# connerctor_3-5v.net
KiCad netlist of a schematic drawn in Altium Designer
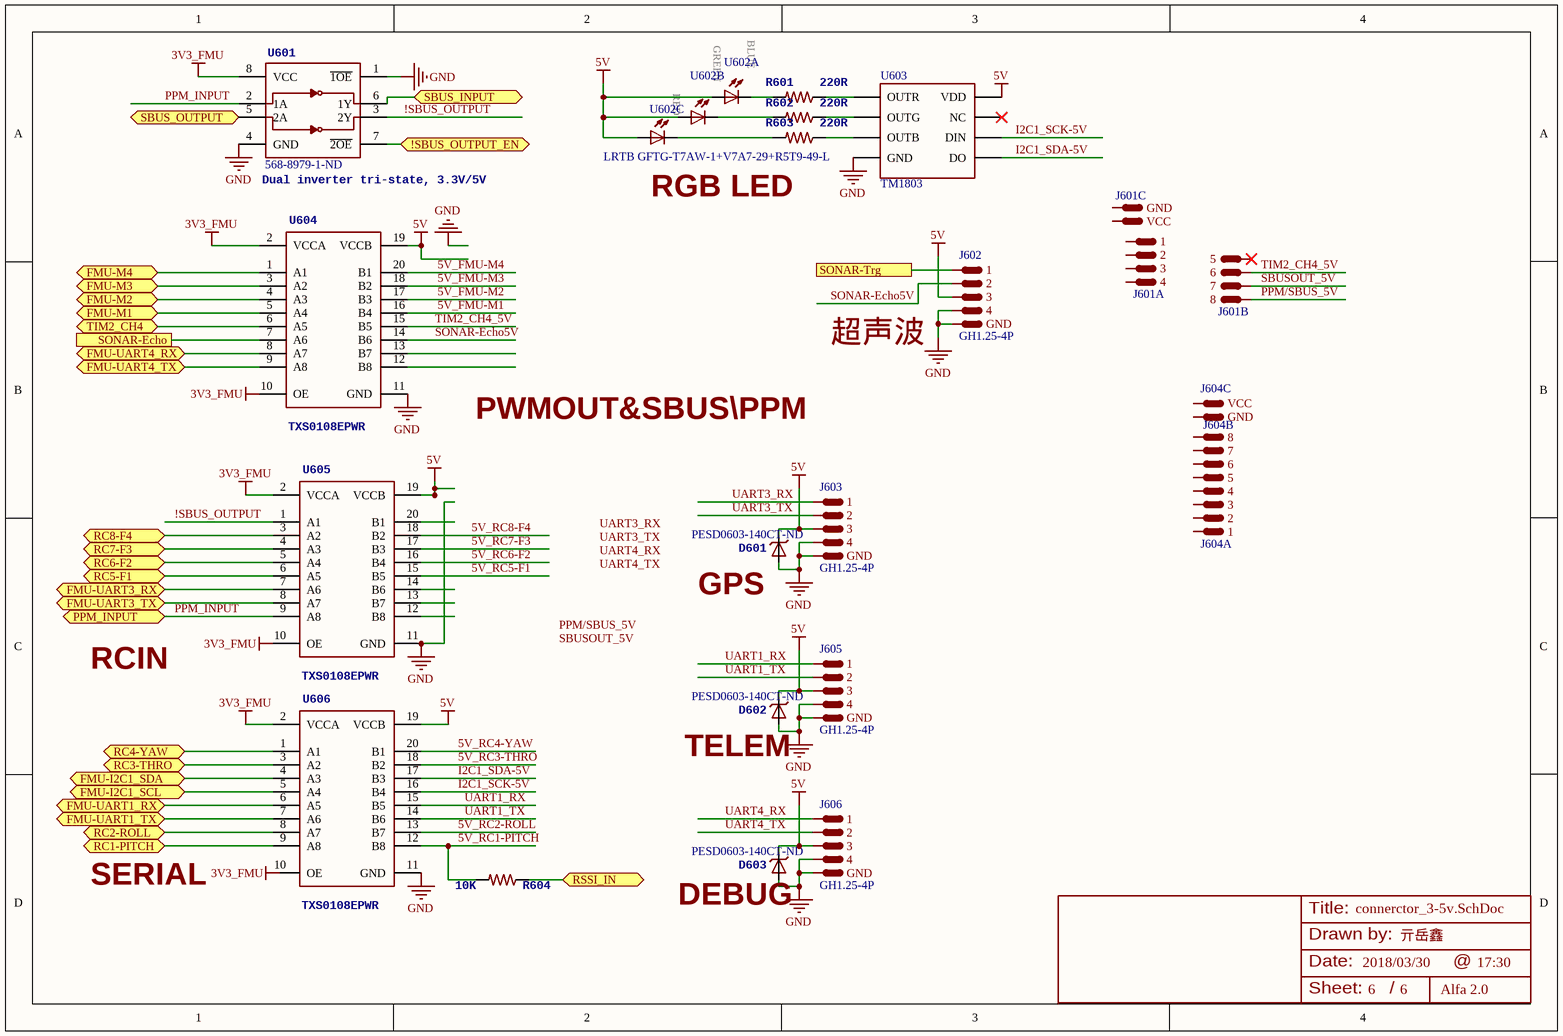
[diagram p0: connerctor_3-5v.SchDoc]

(export (version "E")
  (design (tool "Eeschema 10.0.6"))
  (components
    (comp (ref "D601")
      (value "PESD0603-140")
      (footprint "0603-ESD")
      (description "TVS DIODE 14V 0603")
      (fields (field (name "SUPPLIER PART NUMBER 1") "PESD0603-140CT-ND"))
      (libsource (lib "Q's无源元件类") (part "DIODE-ESD"))
    )
    (comp (ref "D602")
      (value "PESD0603-140")
      (footprint "0603-ESD")
      (description "TVS DIODE 14V 0603")
      (fields (field (name "SUPPLIER PART NUMBER 1") "PESD0603-140CT-ND"))
      (libsource (lib "Q's无源元件类") (part "DIODE-ESD"))
    )
    (comp (ref "D603")
      (value "PESD0603-140")
      (footprint "0603-ESD")
      (description "TVS DIODE 14V 0603")
      (fields (field (name "SUPPLIER PART NUMBER 1") "PESD0603-140CT-ND"))
      (libsource (lib "Q's无源元件类") (part "DIODE-ESD"))
    )
    (comp (ref "J601")
      (value "JR 3X8")
      (footprint "JR3X8")
      (description "Header 3X8 pins")
      (libsource (lib "Q's端子及图标") (part "JR 3X8"))
    )
    (comp (ref "J602")
      (value "GH1.25-4P")
      (footprint "1.25-4P")
      (description "GH1.25mm 立贴 间距1.25mm 连接器贴片")
      (libsource (lib "Q's端子及图标") (part "GH1.25-4P"))
    )
    (comp (ref "J603")
      (value "GH1.25-4P")
      (footprint "1.25-4P")
      (description "GH1.25mm 立贴 间距1.25mm 连接器贴片")
      (libsource (lib "Q's端子及图标") (part "GH1.25-4P"))
    )
    (comp (ref "J604")
      (value "JR 3X8")
      (footprint "JR3X8")
      (description "Header 3X8 pins")
      (libsource (lib "Q's端子及图标") (part "JR 3X8"))
    )
    (comp (ref "J605")
      (value "GH1.25-4P")
      (footprint "1.25-4P")
      (description "GH1.25mm 立贴 间距1.25mm 连接器贴片")
      (libsource (lib "Q's端子及图标") (part "GH1.25-4P"))
    )
    (comp (ref "J606")
      (value "GH1.25-4P")
      (footprint "1.25-4P")
      (description "GH1.25mm 立贴 间距1.25mm 连接器贴片")
      (libsource (lib "Q's端子及图标") (part "GH1.25-4P"))
    )
    (comp (ref "R601")
      (value "220R")
      (footprint "0603-RES")
      (description "RES 220R OHM 1/10W 5% 0603")
      (libsource (lib "Q's无源元件类") (part "RES0603-220R"))
    )
    (comp (ref "R602")
      (value "220R")
      (footprint "0603-RES")
      (description "RES 220R OHM 1/10W 5% 0603")
      (libsource (lib "Q's无源元件类") (part "RES0603-220R"))
    )
    (comp (ref "R603")
      (value "220R")
      (footprint "0603-RES")
      (description "RES 220R OHM 1/10W 5% 0603")
      (libsource (lib "Q's无源元件类") (part "RES0603-220R"))
    )
    (comp (ref "R604")
      (value "10K")
      (footprint "0603-RES")
      (description "RES 10K OHM 1/10W 5% 0603")
      (libsource (lib "Q's无源元件类") (part "RES0603-10K"))
    )
    (comp (ref "U601")
      (value "Dual inverter tri-state, 3.3V/5V")
      (footprint "TSSOP8_SOT505-2")
      (description "IC INVERTER DUAL 4-INPUT 8TSSOP")
      (fields
        (field (name "3DR_PARTNO") "ECM0817")
        (field (name "PARTNO") "74LVC2G240DP,125")
        (field (name "SUPPLIER PART NUMBER 1") "568-8979-1-ND")
      )
      (libsource (lib "Q's有源芯片类") (part "74LVC2G240-TSSOP-8"))
    )
    (comp (ref "U602")
      (value "LRTB GFTG-T7AW-1+V7A7-29+R5T9-49-L")
      (footprint "P-LCC-6")
      (description "Muti LEDs")
      (libsource (lib "Q's无源元件类") (part "LED-RGB"))
    )
    (comp (ref "U603")
      (value "TM1803")
      (footprint "SO08")
      (description "3-Channel Constant-Current LED Driver")
      (libsource (lib "Q's有源芯片类") (part "LED_DRV-TM1803"))
    )
    (comp (ref "U604")
      (value "TXS0108EPWR")
      (footprint "SOP65P640-20N")
      (description "IC XLATR VOLT-LVL 8B BDIR 20SOP")
      (libsource (lib "Q's有源芯片类") (part "TXS0108EPWR"))
    )
    (comp (ref "U605")
      (value "TXS0108EPWR")
      (footprint "SOP65P640-20N")
      (description "IC XLATR VOLT-LVL 8B BDIR 20SOP")
      (libsource (lib "Q's有源芯片类") (part "TXS0108EPWR"))
    )
    (comp (ref "U606")
      (value "TXS0108EPWR")
      (footprint "SOP65P640-20N")
      (description "IC XLATR VOLT-LVL 8B BDIR 20SOP")
      (libsource (lib "Q's有源芯片类") (part "TXS0108EPWR"))
    )
  )
  (nets
    (net (code "1") (name "/!SBUS_OUTPUT") (class "Default")
      (node (ref "U601") (pin "3") (pinfunction "2Y_3") (pintype "passive"))
      (node (ref "U605") (pin "1") (pinfunction "A1_1") (pintype "passive"))
    )
    (net (code "2") (name "/!SBUS_OUTPUT_EN") (class "Default")
      (node (ref "U601") (pin "7") (pinfunction "~{2OE}_7") (pintype "passive"))
    )
    (net (code "3") (name "/5V_FMU-M1") (class "Default")
      (node (ref "U604") (pin "16") (pinfunction "B4_16") (pintype "passive"))
    )
    (net (code "4") (name "/5V_FMU-M2") (class "Default")
      (node (ref "U604") (pin "17") (pinfunction "B3_17") (pintype "passive"))
    )
    (net (code "5") (name "/5V_FMU-M3") (class "Default")
      (node (ref "U604") (pin "18") (pinfunction "B2_18") (pintype "passive"))
    )
    (net (code "6") (name "/5V_FMU-M4") (class "Default")
      (node (ref "U604") (pin "20") (pinfunction "B1_20") (pintype "passive"))
    )
    (net (code "7") (name "/5V_RC1-PITCH") (class "Default")
      (node (ref "R604") (pin "2") (pinfunction "2_2") (pintype "passive"))
      (node (ref "U606") (pin "12") (pinfunction "B8_12") (pintype "passive"))
    )
    (net (code "8") (name "/5V_RC2-ROLL") (class "Default")
      (node (ref "U606") (pin "13") (pinfunction "B7_13") (pintype "passive"))
    )
    (net (code "9") (name "/5V_RC3-THRO") (class "Default")
      (node (ref "U606") (pin "18") (pinfunction "B2_18") (pintype "passive"))
    )
    (net (code "10") (name "/5V_RC4-YAW") (class "Default")
      (node (ref "U606") (pin "20") (pinfunction "B1_20") (pintype "passive"))
    )
    (net (code "11") (name "/5V_RC5-F1") (class "Default")
      (node (ref "U605") (pin "15") (pinfunction "B5_15") (pintype "passive"))
    )
    (net (code "12") (name "/5V_RC6-F2") (class "Default")
      (node (ref "U605") (pin "16") (pinfunction "B4_16") (pintype "passive"))
    )
    (net (code "13") (name "/5V_RC7-F3") (class "Default")
      (node (ref "U605") (pin "17") (pinfunction "B3_17") (pintype "passive"))
    )
    (net (code "14") (name "/5V_RC8-F4") (class "Default")
      (node (ref "U605") (pin "18") (pinfunction "B2_18") (pintype "passive"))
    )
    (net (code "15") (name "/FMU-I2C1_SCL") (class "Default")
      (node (ref "U606") (pin "5") (pinfunction "A4_5") (pintype "passive"))
    )
    (net (code "16") (name "/FMU-I2C1_SDA") (class "Default")
      (node (ref "U606") (pin "4") (pinfunction "A3_4") (pintype "passive"))
    )
    (net (code "17") (name "/FMU-M1") (class "Default")
      (node (ref "U604") (pin "5") (pinfunction "A4_5") (pintype "passive"))
    )
    (net (code "18") (name "/FMU-M2") (class "Default")
      (node (ref "U604") (pin "4") (pinfunction "A3_4") (pintype "passive"))
    )
    (net (code "19") (name "/FMU-M3") (class "Default")
      (node (ref "U604") (pin "3") (pinfunction "A2_3") (pintype "passive"))
    )
    (net (code "20") (name "/FMU-M4") (class "Default")
      (node (ref "U604") (pin "1") (pinfunction "A1_1") (pintype "passive"))
    )
    (net (code "21") (name "/FMU-UART1_RX") (class "Default")
      (node (ref "U606") (pin "6") (pinfunction "A5_6") (pintype "passive"))
    )
    (net (code "22") (name "/FMU-UART1_TX") (class "Default")
      (node (ref "U606") (pin "7") (pinfunction "A6_7") (pintype "passive"))
    )
    (net (code "23") (name "/FMU-UART3_RX") (class "Default")
      (node (ref "U605") (pin "7") (pinfunction "A6_7") (pintype "passive"))
    )
    (net (code "24") (name "/FMU-UART3_TX") (class "Default")
      (node (ref "U605") (pin "8") (pinfunction "A7_8") (pintype "passive"))
    )
    (net (code "25") (name "/FMU-UART4_RX") (class "Default")
      (node (ref "U604") (pin "8") (pinfunction "A7_8") (pintype "passive"))
    )
    (net (code "26") (name "/FMU-UART4_TX") (class "Default")
      (node (ref "U604") (pin "9") (pinfunction "A8_9") (pintype "passive"))
    )
    (net (code "27") (name "/I2C1_SCK-5V") (class "Default")
      (node (ref "U603") (pin "6") (pinfunction "DIN_6") (pintype "passive"))
      (node (ref "U606") (pin "16") (pinfunction "B4_16") (pintype "passive"))
    )
    (net (code "28") (name "/I2C1_SDA-5V") (class "Default")
      (node (ref "U603") (pin "5") (pinfunction "DO_5") (pintype "passive"))
      (node (ref "U606") (pin "17") (pinfunction "B3_17") (pintype "passive"))
    )
    (net (code "29") (name "/PPM_INPUT") (class "Default")
      (node (ref "U601") (pin "2") (pinfunction "1A_2") (pintype "passive"))
      (node (ref "U605") (pin "9") (pinfunction "A8_9") (pintype "passive"))
    )
    (net (code "30") (name "/PPM{slash}SBUS_5V") (class "Default")
      (node (ref "J601") (pin "8") (pinfunction "8_8") (pintype "passive"))
    )
    (net (code "31") (name "/RC1-PITCH") (class "Default")
      (node (ref "U606") (pin "9") (pinfunction "A8_9") (pintype "passive"))
    )
    (net (code "32") (name "/RC2-ROLL") (class "Default")
      (node (ref "U606") (pin "8") (pinfunction "A7_8") (pintype "passive"))
    )
    (net (code "33") (name "/RC3-THRO") (class "Default")
      (node (ref "U606") (pin "3") (pinfunction "A2_3") (pintype "passive"))
    )
    (net (code "34") (name "/RC4-YAW") (class "Default")
      (node (ref "U606") (pin "1") (pinfunction "A1_1") (pintype "passive"))
    )
    (net (code "35") (name "/RC5-F1") (class "Default")
      (node (ref "U605") (pin "6") (pinfunction "A5_6") (pintype "passive"))
    )
    (net (code "36") (name "/RC6-F2") (class "Default")
      (node (ref "U605") (pin "5") (pinfunction "A4_5") (pintype "passive"))
    )
    (net (code "37") (name "/RC7-F3") (class "Default")
      (node (ref "U605") (pin "4") (pinfunction "A3_4") (pintype "passive"))
    )
    (net (code "38") (name "/RC8-F4") (class "Default")
      (node (ref "U605") (pin "3") (pinfunction "A2_3") (pintype "passive"))
    )
    (net (code "39") (name "/RSSI_IN") (class "Default")
      (node (ref "R604") (pin "1") (pinfunction "1_1") (pintype "passive"))
    )
    (net (code "40") (name "/SBUSOUT_5V") (class "Default")
      (node (ref "J601") (pin "7") (pinfunction "7_7") (pintype "passive"))
    )
    (net (code "41") (name "/SBUS_INPUT") (class "Default")
      (node (ref "U601") (pin "6") (pinfunction "1Y_6") (pintype "passive"))
    )
    (net (code "42") (name "/SBUS_OUTPUT") (class "Default")
      (node (ref "U601") (pin "5") (pinfunction "2A_5") (pintype "passive"))
    )
    (net (code "43") (name "/SONAR-Echo") (class "Default")
      (node (ref "U604") (pin "7") (pinfunction "A6_7") (pintype "passive"))
    )
    (net (code "44") (name "/SONAR-Echo5V") (class "Default")
      (node (ref "J602") (pin "2") (pinfunction "2_2") (pintype "passive"))
      (node (ref "U604") (pin "14") (pinfunction "B6_14") (pintype "passive"))
    )
    (net (code "45") (name "/SONAR-Trg") (class "Default")
      (node (ref "J602") (pin "1") (pinfunction "1_1") (pintype "passive"))
    )
    (net (code "46") (name "/TIM2_CH4") (class "Default")
      (node (ref "U604") (pin "6") (pinfunction "A5_6") (pintype "passive"))
    )
    (net (code "47") (name "/TIM2_CH4_5V") (class "Default")
      (node (ref "J601") (pin "6") (pinfunction "6_6") (pintype "passive"))
      (node (ref "U604") (pin "15") (pinfunction "B5_15") (pintype "passive"))
    )
    (net (code "48") (name "/UART1_RX") (class "Default")
      (node (ref "J605") (pin "1") (pinfunction "1_1") (pintype "passive"))
      (node (ref "U606") (pin "15") (pinfunction "B5_15") (pintype "passive"))
    )
    (net (code "49") (name "/UART1_TX") (class "Default")
      (node (ref "J605") (pin "2") (pinfunction "2_2") (pintype "passive"))
      (node (ref "U606") (pin "14") (pinfunction "B6_14") (pintype "passive"))
    )
    (net (code "50") (name "/UART3_RX") (class "Default")
      (node (ref "J603") (pin "1") (pinfunction "1_1") (pintype "passive"))
    )
    (net (code "51") (name "/UART3_TX") (class "Default")
      (node (ref "J603") (pin "2") (pinfunction "2_2") (pintype "passive"))
    )
    (net (code "52") (name "/UART4_RX") (class "Default")
      (node (ref "J606") (pin "1") (pinfunction "1_1") (pintype "passive"))
    )
    (net (code "53") (name "/UART4_TX") (class "Default")
      (node (ref "J606") (pin "2") (pinfunction "2_2") (pintype "passive"))
    )
    (net (code "54") (name "3V3_FMU") (class "Default")
      (node (ref "U601") (pin "8") (pinfunction "VCC_8") (pintype "power_in"))
      (node (ref "U604") (pin "10") (pinfunction "OE_10") (pintype "passive"))
      (node (ref "U604") (pin "2") (pinfunction "VCCA_2") (pintype "passive"))
      (node (ref "U605") (pin "10") (pinfunction "OE_10") (pintype "passive"))
      (node (ref "U605") (pin "2") (pinfunction "VCCA_2") (pintype "passive"))
      (node (ref "U606") (pin "2") (pinfunction "VCCA_2") (pintype "passive"))
    )
    (net (code "55") (name "5V") (class "Default")
      (node (ref "D601") (pin "C") (pinfunction "C_C") (pintype "passive"))
      (node (ref "D602") (pin "C") (pinfunction "C_C") (pintype "passive"))
      (node (ref "D603") (pin "C") (pinfunction "C_C") (pintype "passive"))
      (node (ref "J602") (pin "3") (pinfunction "3_3") (pintype "passive"))
      (node (ref "J603") (pin "3") (pinfunction "3_3") (pintype "passive"))
      (node (ref "J605") (pin "3") (pinfunction "3_3") (pintype "passive"))
      (node (ref "J606") (pin "3") (pinfunction "3_3") (pintype "passive"))
      (node (ref "U602") (pin "A1") (pinfunction "A_A1") (pintype "passive"))
      (node (ref "U602") (pin "A2") (pinfunction "A_A2") (pintype "passive"))
      (node (ref "U602") (pin "A3") (pinfunction "A_A3") (pintype "passive"))
      (node (ref "U603") (pin "8") (pinfunction "VDD_8") (pintype "passive"))
      (node (ref "U604") (pin "19") (pinfunction "VCCB_19") (pintype "passive"))
      (node (ref "U605") (pin "19") (pinfunction "VCCB_19") (pintype "passive"))
      (node (ref "U606") (pin "19") (pinfunction "VCCB_19") (pintype "passive"))
    )
    (net (code "56") (name "GND") (class "Default")
      (node (ref "D601") (pin "A") (pinfunction "A_A") (pintype "passive"))
      (node (ref "D602") (pin "A") (pinfunction "A_A") (pintype "passive"))
      (node (ref "D603") (pin "A") (pinfunction "A_A") (pintype "passive"))
      (node (ref "J602") (pin "4") (pinfunction "4_4") (pintype "passive"))
      (node (ref "J602") (pin "GND") (pinfunction "GND_GND") (pintype "passive"))
      (node (ref "J603") (pin "4") (pinfunction "4_4") (pintype "passive"))
      (node (ref "J603") (pin "GND") (pinfunction "GND_GND") (pintype "passive"))
      (node (ref "J605") (pin "4") (pinfunction "4_4") (pintype "passive"))
      (node (ref "J605") (pin "GND") (pinfunction "GND_GND") (pintype "passive"))
      (node (ref "J606") (pin "4") (pinfunction "4_4") (pintype "passive"))
      (node (ref "J606") (pin "GND") (pinfunction "GND_GND") (pintype "passive"))
      (node (ref "U601") (pin "1") (pinfunction "~{1OE}_1") (pintype "passive"))
      (node (ref "U601") (pin "4") (pinfunction "GND_4") (pintype "passive"))
      (node (ref "U603") (pin "4") (pinfunction "GND_4") (pintype "passive"))
      (node (ref "U604") (pin "11") (pinfunction "GND_11") (pintype "passive"))
      (node (ref "U605") (pin "11") (pinfunction "GND_11") (pintype "passive"))
      (node (ref "U606") (pin "11") (pinfunction "GND_11") (pintype "passive"))
    )
    (net (code "57") (name "Net-(U602A-C)") (class "Default")
      (node (ref "R601") (pin "2") (pinfunction "2_2") (pintype "passive"))
      (node (ref "U602") (pin "C1") (pinfunction "C_C1") (pintype "passive"))
    )
    (net (code "58") (name "Net-(U602B-C)") (class "Default")
      (node (ref "R602") (pin "2") (pinfunction "2_2") (pintype "passive"))
      (node (ref "U602") (pin "C2") (pinfunction "C_C2") (pintype "passive"))
    )
    (net (code "59") (name "Net-(U602C-C)") (class "Default")
      (node (ref "R603") (pin "2") (pinfunction "2_2") (pintype "passive"))
      (node (ref "U602") (pin "C3") (pinfunction "C_C3") (pintype "passive"))
    )
    (net (code "60") (name "Net-(U603-OUTB)") (class "Default")
      (node (ref "R603") (pin "1") (pinfunction "1_1") (pintype "passive"))
      (node (ref "U603") (pin "3") (pinfunction "OUTB_3") (pintype "passive"))
    )
    (net (code "61") (name "Net-(U603-OUTG)") (class "Default")
      (node (ref "R602") (pin "1") (pinfunction "1_1") (pintype "passive"))
      (node (ref "U603") (pin "2") (pinfunction "OUTG_2") (pintype "passive"))
    )
    (net (code "62") (name "Net-(U603-OUTR)") (class "Default")
      (node (ref "R601") (pin "1") (pinfunction "1_1") (pintype "passive"))
      (node (ref "U603") (pin "1") (pinfunction "OUTR_1") (pintype "passive"))
    )
    (net (code "63") (name "unconnected-(J601-Pad1)") (class "Default")
      (node (ref "J601") (pin "1") (pinfunction "1_1") (pintype "passive"))
    )
    (net (code "64") (name "unconnected-(J601-Pad2)") (class "Default")
      (node (ref "J601") (pin "2") (pinfunction "2_2") (pintype "passive"))
    )
    (net (code "65") (name "unconnected-(J601-Pad3)") (class "Default")
      (node (ref "J601") (pin "3") (pinfunction "3_3") (pintype "passive"))
    )
    (net (code "66") (name "unconnected-(J601-Pad4)") (class "Default")
      (node (ref "J601") (pin "4") (pinfunction "4_4") (pintype "passive"))
    )
    (net (code "67") (name "unconnected-(J601-Pad5)") (class "Default")
      (node (ref "J601") (pin "5") (pinfunction "5_5") (pintype "passive+no_connect"))
    )
    (net (code "68") (name "unconnected-(J601-PadGND)") (class "Default")
      (node (ref "J601") (pin "GND") (pinfunction "GND_GND") (pintype "passive"))
    )
    (net (code "69") (name "unconnected-(J601-PadVCC)") (class "Default")
      (node (ref "J601") (pin "VCC") (pinfunction "VCC_VCC") (pintype "passive"))
    )
    (net (code "70") (name "unconnected-(J604-Pad1)") (class "Default")
      (node (ref "J604") (pin "1") (pinfunction "1_1") (pintype "passive"))
    )
    (net (code "71") (name "unconnected-(J604-Pad2)") (class "Default")
      (node (ref "J604") (pin "2") (pinfunction "2_2") (pintype "passive"))
    )
    (net (code "72") (name "unconnected-(J604-Pad3)") (class "Default")
      (node (ref "J604") (pin "3") (pinfunction "3_3") (pintype "passive"))
    )
    (net (code "73") (name "unconnected-(J604-Pad4)") (class "Default")
      (node (ref "J604") (pin "4") (pinfunction "4_4") (pintype "passive"))
    )
    (net (code "74") (name "unconnected-(J604-Pad5)") (class "Default")
      (node (ref "J604") (pin "5") (pinfunction "5_5") (pintype "passive"))
    )
    (net (code "75") (name "unconnected-(J604-Pad6)") (class "Default")
      (node (ref "J604") (pin "6") (pinfunction "6_6") (pintype "passive"))
    )
    (net (code "76") (name "unconnected-(J604-Pad7)") (class "Default")
      (node (ref "J604") (pin "7") (pinfunction "7_7") (pintype "passive"))
    )
    (net (code "77") (name "unconnected-(J604-Pad8)") (class "Default")
      (node (ref "J604") (pin "8") (pinfunction "8_8") (pintype "passive"))
    )
    (net (code "78") (name "unconnected-(J604-PadGND)") (class "Default")
      (node (ref "J604") (pin "GND") (pinfunction "GND_GND") (pintype "passive"))
    )
    (net (code "79") (name "unconnected-(J604-PadVCC)") (class "Default")
      (node (ref "J604") (pin "VCC") (pinfunction "VCC_VCC") (pintype "passive"))
    )
    (net (code "80") (name "unconnected-(U603-NC-Pad7)") (class "Default")
      (node (ref "U603") (pin "7") (pinfunction "NC_7") (pintype "passive+no_connect"))
    )
    (net (code "81") (name "unconnected-(U604-B7-Pad13)") (class "Default")
      (node (ref "U604") (pin "13") (pinfunction "B7_13") (pintype "passive"))
    )
    (net (code "82") (name "unconnected-(U604-B8-Pad12)") (class "Default")
      (node (ref "U604") (pin "12") (pinfunction "B8_12") (pintype "passive"))
    )
    (net (code "83") (name "unconnected-(U605-B1-Pad20)") (class "Default")
      (node (ref "U605") (pin "20") (pinfunction "B1_20") (pintype "passive"))
    )
    (net (code "84") (name "unconnected-(U605-B6-Pad14)") (class "Default")
      (node (ref "U605") (pin "14") (pinfunction "B6_14") (pintype "passive"))
    )
    (net (code "85") (name "unconnected-(U605-B7-Pad13)") (class "Default")
      (node (ref "U605") (pin "13") (pinfunction "B7_13") (pintype "passive"))
    )
    (net (code "86") (name "unconnected-(U605-B8-Pad12)") (class "Default")
      (node (ref "U605") (pin "12") (pinfunction "B8_12") (pintype "passive"))
    )
    (net (code "87") (name "unconnected-(U606-OE-Pad10)") (class "Default")
      (node (ref "U606") (pin "10") (pinfunction "OE_10") (pintype "passive"))
    )
  )
)
